# Power_FE.net
KiCad netlist of a schematic drawn in Altium Designer
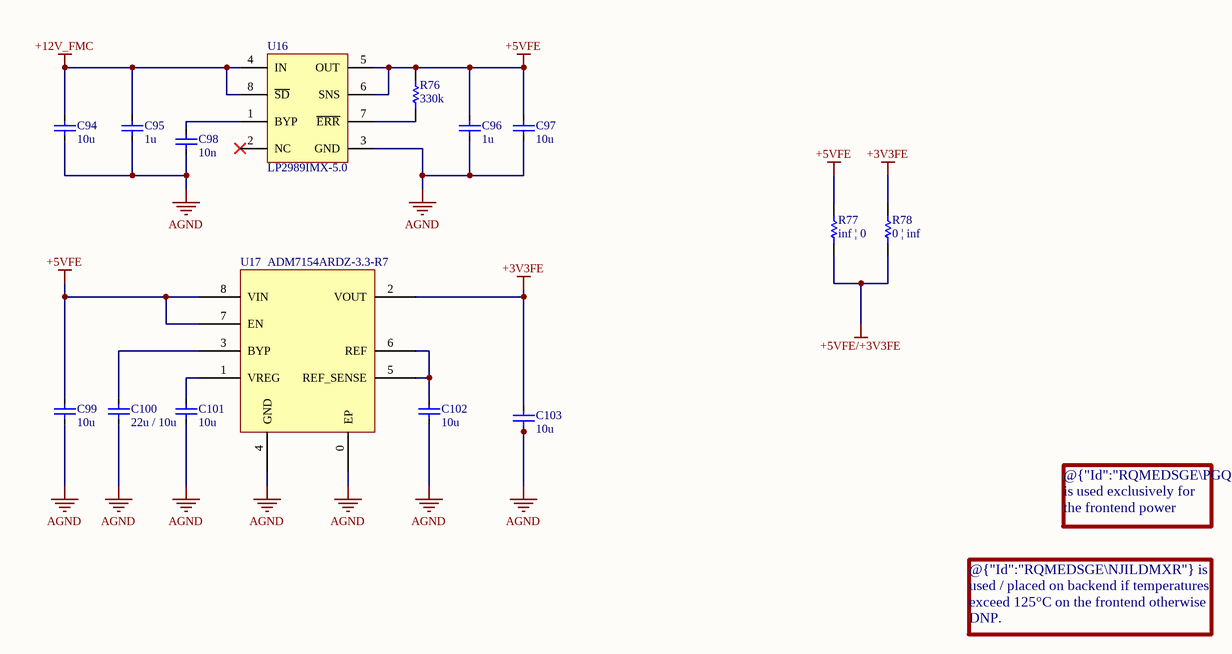
[diagram p0: Power_FE.SchDoc]

(export (version "E")
  (design (tool "Eeschema 10.0.6"))
  (components
    (comp (ref "C94") (value "10u") (footprint "CAP_0603") (libsource (lib "IIS-Lib_TW") (part "Cap")))
    (comp (ref "C95") (value "1u") (footprint "CAP_0402") (libsource (lib "IIS-Lib_TW") (part "Cap")))
    (comp (ref "C96")
      (value "1u")
      (footprint "IIS-Lib_TW:CAP_0402")
      (libsource (lib "IIS-Lib_TW") (part "Cap"))
    )
    (comp (ref "C97") (value "10u") (footprint "CAP_0603") (libsource (lib "IIS-Lib_TW") (part "Cap")))
    (comp (ref "C98") (value "10n") (footprint "CAP_0402") (libsource (lib "IIS-Lib_TW") (part "Cap")))
    (comp (ref "C99")
      (value "10u")
      (footprint "IIS-Lib_TW:CAP_0603")
      (libsource (lib "IIS-Lib_TW") (part "Cap"))
    )
    (comp (ref "C100")
      (value "22u / 10u")
      (footprint "IIS-Lib_TW:CAP_0603")
      (libsource (lib "IIS-Lib_TW") (part "Cap"))
    )
    (comp (ref "C101")
      (value "10u")
      (footprint "IIS-Lib_TW:CAP_0603")
      (libsource (lib "IIS-Lib_TW") (part "Cap"))
    )
    (comp (ref "C102")
      (value "10u")
      (footprint "IIS-Lib_TW:CAP_0603")
      (libsource (lib "IIS-Lib_TW") (part "Cap"))
    )
    (comp (ref "C103")
      (value "10u")
      (footprint "IIS-Lib_TW:CAP_0603")
      (libsource (lib "IIS-Lib_TW") (part "Cap"))
    )
    (comp (ref "R76") (value "330k") (footprint "RES_0402") (libsource (lib "IIS-Lib_TW") (part "Res")))
    (comp (ref "R77") (value "inf ¦ 0") (footprint "RES_0402") (libsource (lib "IIS-Lib_TW") (part "Res")))
    (comp (ref "R78") (value "0 ¦ inf") (footprint "RES_0402") (libsource (lib "IIS-Lib_TW") (part "Res")))
    (comp (ref "U16")
      (value "LP2989IMX-5.0")
      (footprint "SOP127P600X175-8N")
      (libsource (lib "IIS-Lib_TW") (part "LP2989"))
    )
    (comp (ref "U17")
      (value "ADM7154ARDZ-3.3-R7")
      (footprint "IIS-Lib_TW:SOIC-8_TP - TW")
      (libsource (lib "IIS-Lib_TW") (part "ADM715X"))
    )
  )
  (nets
    (net (code "1") (name "+3V3FE") (class "Default")
      (node (ref "C103") (pin "1") (pinfunction "1_1") (pintype "passive"))
      (node (ref "R78") (pin "2") (pinfunction "2_2") (pintype "passive"))
      (node (ref "U17") (pin "2") (pinfunction "VOUT_2") (pintype "passive"))
    )
    (net (code "2") (name "+5VFE") (class "Default")
      (node (ref "C96") (pin "1") (pinfunction "1_1") (pintype "passive"))
      (node (ref "C97") (pin "1") (pinfunction "1_1") (pintype "passive"))
      (node (ref "C99") (pin "1") (pinfunction "1_1") (pintype "passive"))
      (node (ref "R76") (pin "2") (pinfunction "2_2") (pintype "passive"))
      (node (ref "R77") (pin "2") (pinfunction "2_2") (pintype "passive"))
      (node (ref "U16") (pin "5") (pinfunction "OUT_5") (pintype "passive"))
      (node (ref "U16") (pin "6") (pinfunction "SNS_6") (pintype "passive"))
      (node (ref "U17") (pin "7") (pinfunction "EN_7") (pintype "passive"))
      (node (ref "U17") (pin "8") (pinfunction "VIN_8") (pintype "passive"))
    )
    (net (code "3") (name "+5VFE{slash}+3V3FE") (class "Default")
      (node (ref "R77") (pin "1") (pinfunction "1_1") (pintype "passive"))
      (node (ref "R78") (pin "1") (pinfunction "1_1") (pintype "passive"))
    )
    (net (code "4") (name "+12V_FMC") (class "Default")
      (node (ref "C94") (pin "1") (pinfunction "1_1") (pintype "passive"))
      (node (ref "C95") (pin "1") (pinfunction "1_1") (pintype "passive"))
      (node (ref "U16") (pin "4") (pinfunction "IN_4") (pintype "passive"))
      (node (ref "U16") (pin "8") (pinfunction "~{SD}_8") (pintype "passive"))
    )
    (net (code "5") (name "AGND") (class "Default")
      (node (ref "C100") (pin "2") (pinfunction "2_2") (pintype "passive"))
      (node (ref "C101") (pin "2") (pinfunction "2_2") (pintype "passive"))
      (node (ref "C102") (pin "2") (pinfunction "2_2") (pintype "passive"))
      (node (ref "C103") (pin "2") (pinfunction "2_2") (pintype "passive"))
      (node (ref "C94") (pin "2") (pinfunction "2_2") (pintype "passive"))
      (node (ref "C95") (pin "2") (pinfunction "2_2") (pintype "passive"))
      (node (ref "C96") (pin "2") (pinfunction "2_2") (pintype "passive"))
      (node (ref "C97") (pin "2") (pinfunction "2_2") (pintype "passive"))
      (node (ref "C98") (pin "2") (pinfunction "2_2") (pintype "passive"))
      (node (ref "C99") (pin "2") (pinfunction "2_2") (pintype "passive"))
      (node (ref "U16") (pin "3") (pinfunction "GND_3") (pintype "passive"))
      (node (ref "U17") (pin "0") (pinfunction "EP_0") (pintype "passive"))
      (node (ref "U17") (pin "4") (pinfunction "GND_4") (pintype "passive"))
    )
    (net (code "6") (name "Net-(U16-BYP)") (class "Default")
      (node (ref "C98") (pin "1") (pinfunction "1_1") (pintype "passive"))
      (node (ref "U16") (pin "1") (pinfunction "BYP_1") (pintype "passive"))
    )
    (net (code "7") (name "Net-(U16-~{ERR})") (class "Default")
      (node (ref "R76") (pin "1") (pinfunction "1_1") (pintype "passive"))
      (node (ref "U16") (pin "7") (pinfunction "~{ERR}_7") (pintype "passive"))
    )
    (net (code "8") (name "Net-(U17-BYP)") (class "Default")
      (node (ref "C100") (pin "1") (pinfunction "1_1") (pintype "passive"))
      (node (ref "U17") (pin "3") (pinfunction "BYP_3") (pintype "passive"))
    )
    (net (code "9") (name "Net-(U17-REF)") (class "Default")
      (node (ref "C102") (pin "1") (pinfunction "1_1") (pintype "passive"))
      (node (ref "U17") (pin "5") (pinfunction "REF_SENSE_5") (pintype "passive"))
      (node (ref "U17") (pin "6") (pinfunction "REF_6") (pintype "passive"))
    )
    (net (code "10") (name "Net-(U17-VREG)") (class "Default")
      (node (ref "C101") (pin "1") (pinfunction "1_1") (pintype "passive"))
      (node (ref "U17") (pin "1") (pinfunction "VREG_1") (pintype "passive"))
    )
    (net (code "11") (name "unconnected-(U16-NC-Pad2)") (class "Default")
      (node (ref "U16") (pin "2") (pinfunction "NC_2") (pintype "passive+no_connect"))
    )
  )
)
